# DelSolClock_Rear.net
KiCad netlist of a schematic drawn in Altium Designer
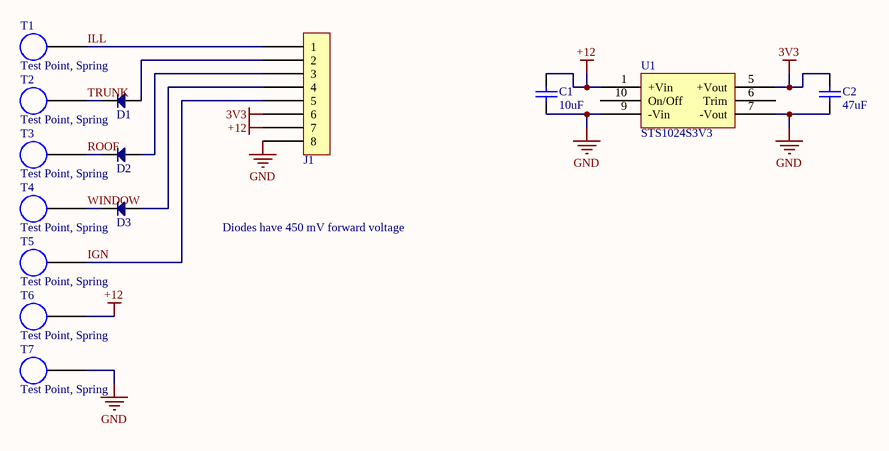
[diagram p0: DelSolClock_Rear.SchDoc]

(export (version "E")
  (design (tool "Eeschema 10.0.6"))
  (components
    (comp (ref "C1")
      (value "10uF")
      (footprint "6-0805")
      (description "Capacitor")
      (fields (field (name "Comment") "C2012X5R1E106K085AC"))
      (libsource (lib "DiscreteComponents") (part "Cap"))
    )
    (comp (ref "C2")
      (value "47uF")
      (footprint "6-0805")
      (description "Capacitor")
      (fields (field (name "Comment") "GRM21BR61A476ME15L"))
      (libsource (lib "DiscreteComponents") (part "Cap"))
    )
    (comp (ref "D1")
      (value "SD0805S020S1R0")
      (footprint "0805 HD - Polarized")
      (description "Diode")
      (fields (field (name "MFG") "Panasonic - ECG"))
      (libsource (lib "DiscreteComponents") (part "Diode"))
    )
    (comp (ref "D2")
      (value "SD0805S020S1R0")
      (footprint "0805 HD - Polarized")
      (description "Diode")
      (fields (field (name "MFG") "Panasonic - ECG"))
      (libsource (lib "DiscreteComponents") (part "Diode"))
    )
    (comp (ref "D3")
      (value "SD0805S020S1R0")
      (footprint "0805 HD - Polarized")
      (description "Diode")
      (fields (field (name "MFG") "Panasonic - ECG"))
      (libsource (lib "DiscreteComponents") (part "Diode"))
    )
    (comp (ref "J1")
      (value "68000-408HLF")
      (footprint "Conn, Header, 8x1 0.1 Pitch Unshrouded")
      (description "Header, 8x1 0.1\" Unshrouded Tin")
      (fields (field (name "MFG") "FCI"))
      (libsource (lib "Connectors") (part "Conn, 68000-408HLF"))
    )
    (comp (ref "T1")
      (value "Test Point, Spring")
      (footprint "Test Point, Spring")
      (description "Test Point, for Del Sol Clock connection")
      (libsource (lib "Connectors") (part "Test Point, Spring"))
    )
    (comp (ref "T2")
      (value "Test Point, Spring")
      (footprint "Test Point, Spring")
      (description "Test Point, for Del Sol Clock connection")
      (libsource (lib "Connectors") (part "Test Point, Spring"))
    )
    (comp (ref "T3")
      (value "Test Point, Spring")
      (footprint "Test Point, Spring")
      (description "Test Point, for Del Sol Clock connection")
      (libsource (lib "Connectors") (part "Test Point, Spring"))
    )
    (comp (ref "T4")
      (value "Test Point, Spring")
      (footprint "Test Point, Spring")
      (description "Test Point, for Del Sol Clock connection")
      (libsource (lib "Connectors") (part "Test Point, Spring"))
    )
    (comp (ref "T5")
      (value "Test Point, Spring")
      (footprint "Test Point, Spring")
      (description "Test Point, for Del Sol Clock connection")
      (libsource (lib "Connectors") (part "Test Point, Spring"))
    )
    (comp (ref "T6")
      (value "Test Point, Spring")
      (footprint "Test Point, Spring")
      (description "Test Point, for Del Sol Clock connection")
      (libsource (lib "Connectors") (part "Test Point, Spring"))
    )
    (comp (ref "T7")
      (value "Test Point, Spring")
      (footprint "Test Point, Spring")
      (description "Test Point, for Del Sol Clock connection")
      (libsource (lib "Connectors") (part "Test Point, Spring"))
    )
    (comp (ref "U1")
      (value "STS1024S3V3")
      (footprint "Module, STS1024S3V3")
      (description "Module, Regulator switching 3.3V 1A out 4.75-36v in SMT")
      (fields (field (name "MFG") "XP Power"))
      (libsource (lib "Modules") (part "Module, STS1024S3V3"))
    )
  )
  (nets
    (net (code "1") (name "+12") (class "Default")
      (node (ref "C1") (pin "2") (pinfunction "2_2") (pintype "passive"))
      (node (ref "J1") (pin "7") (pinfunction "7_7") (pintype "passive"))
      (node (ref "T6") (pin "1") (pintype "passive"))
      (node (ref "U1") (pin "1") (pinfunction "+Vin_1") (pintype "passive"))
    )
    (net (code "2") (name "/IGN") (class "Default")
      (node (ref "J1") (pin "5") (pinfunction "5_5") (pintype "passive"))
      (node (ref "T5") (pin "1") (pintype "passive"))
    )
    (net (code "3") (name "/ILL") (class "Default")
      (node (ref "J1") (pin "1") (pinfunction "1_1") (pintype "passive"))
      (node (ref "T1") (pin "1") (pintype "passive"))
    )
    (net (code "4") (name "/ROOF") (class "Default")
      (node (ref "D2") (pin "1") (pinfunction "C_1") (pintype "passive"))
      (node (ref "T3") (pin "1") (pintype "passive"))
    )
    (net (code "5") (name "/TRUNK") (class "Default")
      (node (ref "D1") (pin "1") (pinfunction "C_1") (pintype "passive"))
      (node (ref "T2") (pin "1") (pintype "passive"))
    )
    (net (code "6") (name "/WINDOW") (class "Default")
      (node (ref "D3") (pin "1") (pinfunction "C_1") (pintype "passive"))
      (node (ref "T4") (pin "1") (pintype "passive"))
    )
    (net (code "7") (name "3V3") (class "Default")
      (node (ref "C2") (pin "2") (pinfunction "2_2") (pintype "passive"))
      (node (ref "J1") (pin "6") (pinfunction "6_6") (pintype "passive"))
      (node (ref "U1") (pin "5") (pinfunction "+Vout_5") (pintype "passive"))
    )
    (net (code "8") (name "GND") (class "Default")
      (node (ref "C1") (pin "1") (pinfunction "1_1") (pintype "passive"))
      (node (ref "C2") (pin "1") (pinfunction "1_1") (pintype "passive"))
      (node (ref "J1") (pin "8") (pinfunction "8_8") (pintype "passive"))
      (node (ref "T7") (pin "1") (pintype "passive"))
      (node (ref "U1") (pin "7") (pinfunction "-Vout_7") (pintype "passive"))
      (node (ref "U1") (pin "9") (pinfunction "-Vin_9") (pintype "passive"))
    )
    (net (code "9") (name "Net-(D1-A)") (class "Default")
      (node (ref "D1") (pin "2") (pinfunction "A_2") (pintype "passive"))
      (node (ref "J1") (pin "2") (pinfunction "2_2") (pintype "passive"))
    )
    (net (code "10") (name "Net-(D2-A)") (class "Default")
      (node (ref "D2") (pin "2") (pinfunction "A_2") (pintype "passive"))
      (node (ref "J1") (pin "3") (pinfunction "3_3") (pintype "passive"))
    )
    (net (code "11") (name "Net-(D3-A)") (class "Default")
      (node (ref "D3") (pin "2") (pinfunction "A_2") (pintype "passive"))
      (node (ref "J1") (pin "4") (pinfunction "4_4") (pintype "passive"))
    )
    (net (code "12") (name "unconnected-(U1-On{slash}Off-Pad10)") (class "Default")
      (node (ref "U1") (pin "10") (pinfunction "On/Off_10") (pintype "passive"))
    )
    (net (code "13") (name "unconnected-(U1-Trim-Pad6)") (class "Default")
      (node (ref "U1") (pin "6") (pinfunction "Trim_6") (pintype "passive"))
    )
  )
)
